# Session_3_Task_V3.net
KiCad netlist of a schematic drawn in EAGLE
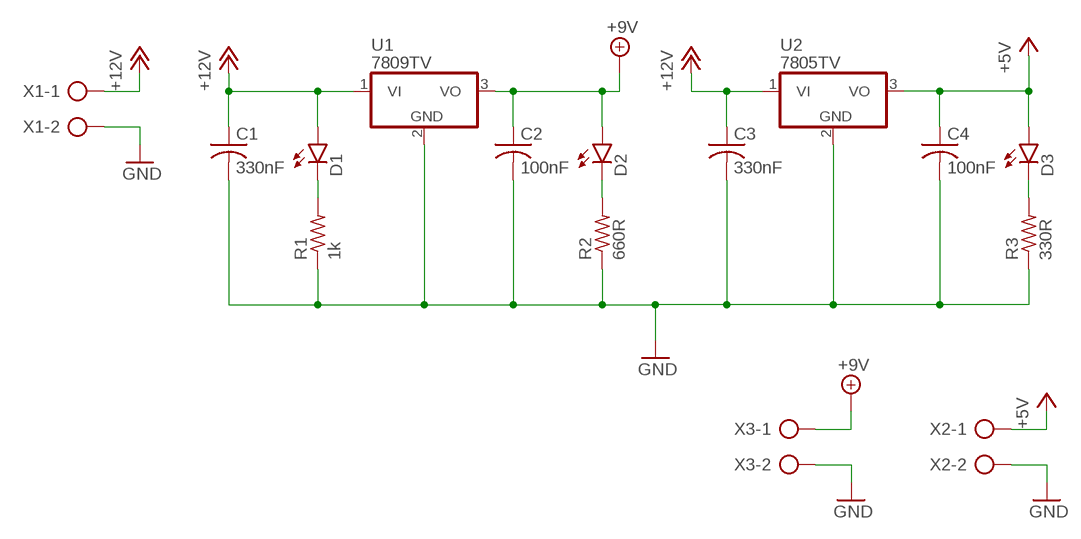
[diagram p0: schematic, sheet 1]

(export (version "E")
  (design (tool "Eeschema 10.0.6"))
  (components
    (comp (ref "C1")
      (value "330nF")
      (footprint "eagle-import:C025-024X044")
      (libsource (lib "eagle-import") (part "C-US025-024X044"))
    )
    (comp (ref "C2")
      (value "100nF")
      (footprint "eagle-import:C025-024X044")
      (libsource (lib "eagle-import") (part "C-US025-024X044"))
    )
    (comp (ref "C3")
      (value "330nF")
      (footprint "eagle-import:C025-024X044")
      (libsource (lib "eagle-import") (part "C-US025-024X044"))
    )
    (comp (ref "C4")
      (value "100nF")
      (footprint "eagle-import:C025-024X044")
      (libsource (lib "eagle-import") (part "C-US025-024X044"))
    )
    (comp (ref "D1")
      (value "LED5MM")
      (footprint "eagle-import:LED5MM")
      (libsource (lib "eagle-import") (part "LED5MM"))
    )
    (comp (ref "D2")
      (value "LED5MM")
      (footprint "eagle-import:LED5MM")
      (libsource (lib "eagle-import") (part "LED5MM"))
    )
    (comp (ref "D3")
      (value "LED5MM")
      (footprint "eagle-import:LED5MM")
      (libsource (lib "eagle-import") (part "LED5MM"))
    )
    (comp (ref "R1")
      (value "1k")
      (footprint "eagle-import:0204_7")
      (libsource (lib "eagle-import") (part "R-US_0204/7"))
    )
    (comp (ref "R2")
      (value "660R")
      (footprint "eagle-import:0204_7")
      (libsource (lib "eagle-import") (part "R-US_0204/7"))
    )
    (comp (ref "R3")
      (value "330R")
      (footprint "eagle-import:0204_7")
      (libsource (lib "eagle-import") (part "R-US_0204/7"))
    )
    (comp (ref "U1")
      (value "7809TV")
      (footprint "eagle-import:TO220V")
      (libsource (lib "eagle-import") (part "78TV05"))
    )
    (comp (ref "U2")
      (value "7805TV")
      (footprint "eagle-import:TO220V")
      (libsource (lib "eagle-import") (part "78TV05"))
    )
    (comp (ref "X1")
      (value "AK500/2")
      (footprint "eagle-import:AK500_2")
      (libsource (lib "eagle-import") (part "AK500/2"))
    )
    (comp (ref "X2")
      (value "AK500/2")
      (footprint "eagle-import:AK500_2")
      (libsource (lib "eagle-import") (part "AK500/2"))
    )
    (comp (ref "X3")
      (value "AK500/2")
      (footprint "eagle-import:AK500_2")
      (libsource (lib "eagle-import") (part "AK500/2"))
    )
  )
  (nets
    (net (code "1") (name "+5V") (class "Default")
      (node (ref "C4") (pin "1") (pinfunction "1_1") (pintype "passive"))
      (node (ref "D3") (pin "A") (pinfunction "A_A") (pintype "passive"))
      (node (ref "U2") (pin "3") (pinfunction "VO_3") (pintype "passive"))
      (node (ref "X2") (pin "1") (pinfunction "KL_1") (pintype "passive"))
    )
    (net (code "2") (name "+9V") (class "Default")
      (node (ref "C2") (pin "1") (pinfunction "1_1") (pintype "passive"))
      (node (ref "D2") (pin "A") (pinfunction "A_A") (pintype "passive"))
      (node (ref "U1") (pin "3") (pinfunction "VO_3") (pintype "passive"))
      (node (ref "X3") (pin "1") (pinfunction "KL_1") (pintype "passive"))
    )
    (net (code "3") (name "+12V") (class "Default")
      (node (ref "C1") (pin "1") (pinfunction "1_1") (pintype "passive"))
      (node (ref "C3") (pin "1") (pinfunction "1_1") (pintype "passive"))
      (node (ref "D1") (pin "A") (pinfunction "A_A") (pintype "passive"))
      (node (ref "U1") (pin "1") (pinfunction "VI_1") (pintype "input"))
      (node (ref "U2") (pin "1") (pinfunction "VI_1") (pintype "input"))
      (node (ref "X1") (pin "1") (pinfunction "KL_1") (pintype "passive"))
    )
    (net (code "4") (name "GND") (class "Default")
      (node (ref "C1") (pin "2") (pinfunction "2_2") (pintype "passive"))
      (node (ref "C2") (pin "2") (pinfunction "2_2") (pintype "passive"))
      (node (ref "C3") (pin "2") (pinfunction "2_2") (pintype "passive"))
      (node (ref "C4") (pin "2") (pinfunction "2_2") (pintype "passive"))
      (node (ref "R1") (pin "1") (pinfunction "1_1") (pintype "passive"))
      (node (ref "R2") (pin "1") (pinfunction "1_1") (pintype "passive"))
      (node (ref "R3") (pin "1") (pinfunction "1_1") (pintype "passive"))
      (node (ref "U1") (pin "2") (pinfunction "GND_2") (pintype "passive"))
      (node (ref "U2") (pin "2") (pinfunction "GND_2") (pintype "passive"))
      (node (ref "X1") (pin "2") (pinfunction "KL_2") (pintype "passive"))
      (node (ref "X2") (pin "2") (pinfunction "KL_2") (pintype "passive"))
      (node (ref "X3") (pin "2") (pinfunction "KL_2") (pintype "passive"))
    )
    (net (code "5") (name "Net-(D1-C)") (class "Default")
      (node (ref "D1") (pin "K") (pinfunction "C_K") (pintype "passive"))
      (node (ref "R1") (pin "2") (pinfunction "2_2") (pintype "passive"))
    )
    (net (code "6") (name "Net-(D2-C)") (class "Default")
      (node (ref "D2") (pin "K") (pinfunction "C_K") (pintype "passive"))
      (node (ref "R2") (pin "2") (pinfunction "2_2") (pintype "passive"))
    )
    (net (code "7") (name "Net-(D3-C)") (class "Default")
      (node (ref "D3") (pin "K") (pinfunction "C_K") (pintype "passive"))
      (node (ref "R3") (pin "2") (pinfunction "2_2") (pintype "passive"))
    )
  )
)
